# dream-machine.net
KiCad netlist of a schematic drawn in EAGLE
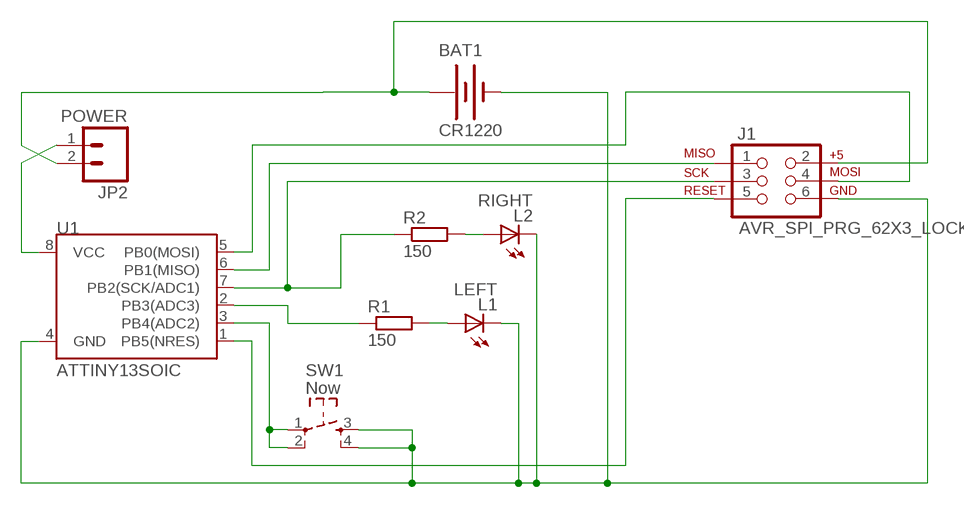
[diagram p0: schematic, sheet 1]

(export (version "E")
  (design (tool "Eeschema 10.0.6"))
  (components
    (comp (ref "BAT1")
      (value "CR1220")
      (footprint "eagle-import:BATTCON_12MM")
      (libsource (lib "eagle-import") (part "BATTERY12MM"))
    )
    (comp (ref "J1")
      (value "AVR_SPI_PRG_62X3_LOCK")
      (footprint "eagle-import:2X3_LOCK")
      (libsource (lib "eagle-import") (part "AVR_SPI_PRG_62X3_LOCK"))
    )
    (comp (ref "JP2")
      (value "POWER")
      (footprint "eagle-import:1X02_LOCK")
      (libsource (lib "eagle-import") (part "M02LOCK"))
    )
    (comp (ref "L1")
      (value "LEFT")
      (footprint "eagle-import:LED-3MM")
      (libsource (lib "eagle-import") (part "LED-3MM"))
    )
    (comp (ref "L2")
      (value "RIGHT")
      (footprint "eagle-import:LED-3MM")
      (libsource (lib "eagle-import") (part "LED-3MM"))
    )
    (comp (ref "R1")
      (value "150")
      (footprint "eagle-import:R805")
      (libsource (lib "eagle-import") (part "RESISTOR-0805R805"))
    )
    (comp (ref "R2")
      (value "150")
      (footprint "eagle-import:R805")
      (libsource (lib "eagle-import") (part "RESISTOR-0805R805"))
    )
    (comp (ref "SW1")
      (value "Now")
      (footprint "eagle-import:SW_TACT_SMALL")
      (libsource (lib "eagle-import") (part "SW_TACT"))
    )
    (comp (ref "U1")
      (value "ATTINY13SOIC")
      (footprint "eagle-import:SO08")
      (libsource (lib "eagle-import") (part "ATTINY13SOIC"))
    )
  )
  (nets
    (net (code "1") (name "Net-(BAT1-+)") (class "Default")
      (node (ref "BAT1") (pin "PWR@1") (pinfunction "+_PWR@1") (pintype "power_in"))
      (node (ref "J1") (pin "2") (pinfunction "2_2") (pintype "passive"))
      (node (ref "JP2") (pin "2") (pinfunction "2_2") (pintype "passive"))
    )
    (net (code "2") (name "Net-(BAT1--)") (class "Default")
      (node (ref "BAT1") (pin "GND") (pinfunction "-_GND") (pintype "power_in"))
      (node (ref "J1") (pin "6") (pinfunction "6_6") (pintype "passive"))
      (node (ref "L1") (pin "K") (pinfunction "C_K") (pintype "passive"))
      (node (ref "L2") (pin "K") (pinfunction "C_K") (pintype "passive"))
      (node (ref "SW1") (pin "3") (pinfunction "3_3") (pintype "passive"))
      (node (ref "SW1") (pin "4") (pinfunction "4_4") (pintype "passive"))
      (node (ref "U1") (pin "4") (pinfunction "GND_4") (pintype "bidirectional"))
    )
    (net (code "3") (name "Net-(L1-PadA)") (class "Default")
      (node (ref "L1") (pin "A") (pinfunction "A_A") (pintype "passive"))
      (node (ref "R1") (pin "2") (pinfunction "2_2") (pintype "passive"))
    )
    (net (code "4") (name "Net-(L2-PadA)") (class "Default")
      (node (ref "L2") (pin "A") (pinfunction "A_A") (pintype "passive"))
      (node (ref "R2") (pin "2") (pinfunction "2_2") (pintype "passive"))
    )
    (net (code "5") (name "Net-(U1-PB0(MOSI))") (class "Default")
      (node (ref "J1") (pin "4") (pinfunction "4_4") (pintype "passive"))
      (node (ref "U1") (pin "5") (pinfunction "PB0(MOSI)_5") (pintype "bidirectional"))
    )
    (net (code "6") (name "Net-(U1-PB1(MISO))") (class "Default")
      (node (ref "J1") (pin "1") (pinfunction "1_1") (pintype "passive"))
      (node (ref "U1") (pin "6") (pinfunction "PB1(MISO)_6") (pintype "bidirectional"))
    )
    (net (code "7") (name "Net-(U1-PB2(SCK{slash}ADC1))") (class "Default")
      (node (ref "J1") (pin "3") (pinfunction "3_3") (pintype "passive"))
      (node (ref "R2") (pin "1") (pinfunction "1_1") (pintype "passive"))
      (node (ref "U1") (pin "7") (pinfunction "PB2(SCK/ADC1)_7") (pintype "bidirectional"))
    )
    (net (code "8") (name "Net-(U1-PB3(ADC3))") (class "Default")
      (node (ref "R1") (pin "1") (pinfunction "1_1") (pintype "passive"))
      (node (ref "U1") (pin "2") (pinfunction "PB3(ADC3)_2") (pintype "bidirectional"))
    )
    (net (code "9") (name "Net-(U1-PB4(ADC2))") (class "Default")
      (node (ref "SW1") (pin "1") (pinfunction "1_1") (pintype "passive"))
      (node (ref "SW1") (pin "2") (pinfunction "2_2") (pintype "passive"))
      (node (ref "U1") (pin "3") (pinfunction "PB4(ADC2)_3") (pintype "bidirectional"))
    )
    (net (code "10") (name "Net-(U1-PB5(NRES))") (class "Default")
      (node (ref "J1") (pin "5") (pinfunction "5_5") (pintype "passive"))
      (node (ref "U1") (pin "1") (pinfunction "PB5(NRES)_1") (pintype "bidirectional"))
    )
    (net (code "11") (name "Net-(U1-VCC)") (class "Default")
      (node (ref "JP2") (pin "1") (pinfunction "1_1") (pintype "passive"))
      (node (ref "U1") (pin "8") (pinfunction "VCC_8") (pintype "bidirectional"))
    )
  )
)
